# Misc.net
KiCad netlist of a schematic drawn in Altium Designer
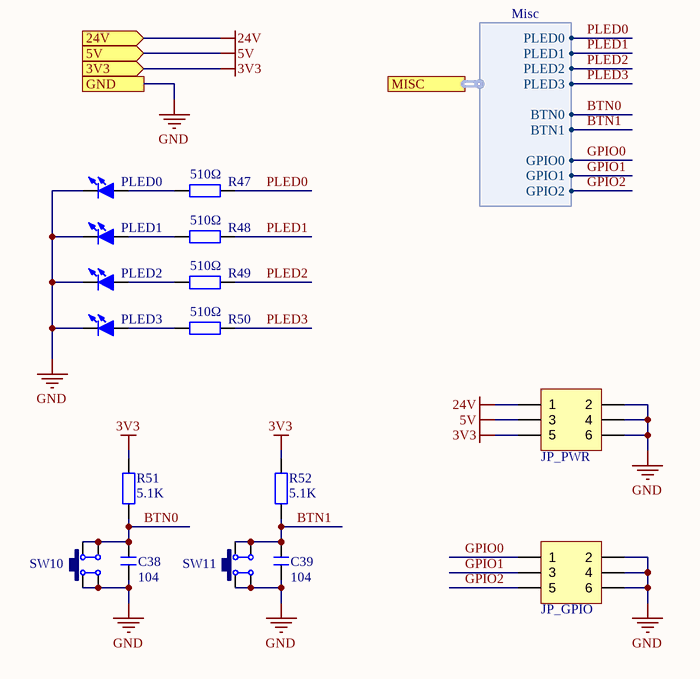
[diagram p0: Misc.SchDoc]

(export (version "E")
  (design (tool "Eeschema 10.0.6"))
  (components
    (comp (ref "C38")
      (value "104")
      (footprint "C 0603_L")
      (description "贴片电容")
      (libsource (lib "0.1 - 电阻-电容-电感") (part "C"))
    )
    (comp (ref "C39")
      (value "104")
      (footprint "C 0603_L")
      (description "贴片电容")
      (libsource (lib "0.1 - 电阻-电容-电感") (part "C"))
    )
    (comp (ref "JP_GPIO")
      (value "Header3X2")
      (footprint "HDR2.54-LI-2x3P")
      (description "3*2P接插件")
      (fields (field (name "版权归属") "封装库来自淘宝 ID：黄晶宝石"))
      (libsource (lib "5.4 - 接插件-脚距2.54 (100mil) ") (part "Header 3X2"))
    )
    (comp (ref "JP_PWR")
      (value "Header3X2")
      (footprint "HDR2.54-LI-2x3P")
      (description "3*2P接插件")
      (fields (field (name "版权归属") "封装库来自淘宝 ID：黄晶宝石"))
      (libsource (lib "5.4 - 接插件-脚距2.54 (100mil) ") (part "Header 3X2"))
    )
    (comp (ref "PLED0")
      (value "Green")
      (footprint "LED 0603G")
      (description "贴片LED")
      (fields (field (name "版权归属") "封装库来自淘宝 ID：黄晶宝石"))
      (libsource (lib "0.3 - LED发光二极管") (part "LED-SMD"))
    )
    (comp (ref "PLED1")
      (value "Green")
      (footprint "LED 0603G")
      (description "贴片LED")
      (fields (field (name "版权归属") "封装库来自淘宝 ID：黄晶宝石"))
      (libsource (lib "0.3 - LED发光二极管") (part "LED-SMD"))
    )
    (comp (ref "PLED2")
      (value "Green")
      (footprint "LED 0603G")
      (description "贴片LED")
      (fields (field (name "版权归属") "封装库来自淘宝 ID：黄晶宝石"))
      (libsource (lib "0.3 - LED发光二极管") (part "LED-SMD"))
    )
    (comp (ref "PLED3")
      (value "Green")
      (footprint "LED 0603G")
      (description "贴片LED")
      (fields (field (name "版权归属") "封装库来自淘宝 ID：黄晶宝石"))
      (libsource (lib "0.3 - LED发光二极管") (part "LED-SMD"))
    )
    (comp (ref "R47")
      (value "510Ω")
      (footprint "R 0603_L")
      (description "贴片电阻")
      (fields (field (name "版权归属") "来自淘宝 ID：黄晶宝石"))
      (libsource (lib "0.1 - 电阻-电容-电感") (part "R"))
    )
    (comp (ref "R48")
      (value "510Ω")
      (footprint "R 0603_L")
      (description "贴片电阻")
      (fields (field (name "版权归属") "来自淘宝 ID：黄晶宝石"))
      (libsource (lib "0.1 - 电阻-电容-电感") (part "R"))
    )
    (comp (ref "R49")
      (value "510Ω")
      (footprint "R 0603_L")
      (description "贴片电阻")
      (fields (field (name "版权归属") "来自淘宝 ID：黄晶宝石"))
      (libsource (lib "0.1 - 电阻-电容-电感") (part "R"))
    )
    (comp (ref "R50")
      (value "510Ω")
      (footprint "R 0603_L")
      (description "贴片电阻")
      (fields (field (name "版权归属") "来自淘宝 ID：黄晶宝石"))
      (libsource (lib "0.1 - 电阻-电容-电感") (part "R"))
    )
    (comp (ref "R51")
      (value "5.1K")
      (footprint "R 0603_L")
      (description "贴片电阻")
      (fields (field (name "版权归属") "来自淘宝 ID：黄晶宝石"))
      (libsource (lib "0.1 - 电阻-电容-电感") (part "R"))
    )
    (comp (ref "R52")
      (value "5.1K")
      (footprint "R 0603_L")
      (description "贴片电阻")
      (fields (field (name "版权归属") "来自淘宝 ID：黄晶宝石"))
      (libsource (lib "0.1 - 电阻-电容-电感") (part "R"))
    )
    (comp (ref "SW10")
      (value "6x6x5")
      (footprint "TSW SMD-6*6*4.3")
      (description "贴片6x6轻触开关 \r\nC3010208")
      (fields (field (name "版权归属") "封装库来自淘宝 ID：黄晶宝石"))
      (libsource (lib "0.7 - 常用按键-开关") (part "TSW SMD-6x6"))
    )
    (comp (ref "SW11")
      (value "6x6x5")
      (footprint "TSW SMD-6*6*4.3")
      (description "贴片6x6轻触开关 \r\nC3010208")
      (fields (field (name "版权归属") "封装库来自淘宝 ID：黄晶宝石"))
      (libsource (lib "0.7 - 常用按键-开关") (part "TSW SMD-6x6"))
    )
  )
  (nets
    (net (code "2") (name "/BTN0") (class "Default")
      (node (ref "C38") (pin "2") (pinfunction "2_2") (pintype "passive"))
      (node (ref "R51") (pin "1") (pinfunction "1_1") (pintype "passive"))
      (node (ref "SW10") (pin "2") (pinfunction "2_2") (pintype "passive"))
      (node (ref "SW10") (pin "3") (pinfunction "3_3") (pintype "passive"))
    )
    (net (code "3") (name "/BTN1") (class "Default")
      (node (ref "C39") (pin "2") (pinfunction "2_2") (pintype "passive"))
      (node (ref "R52") (pin "1") (pinfunction "1_1") (pintype "passive"))
      (node (ref "SW11") (pin "2") (pinfunction "2_2") (pintype "passive"))
      (node (ref "SW11") (pin "3") (pinfunction "3_3") (pintype "passive"))
    )
    (net (code "4") (name "/GPIO0") (class "Default")
      (node (ref "JP_GPIO") (pin "1") (pinfunction "1_1") (pintype "passive"))
    )
    (net (code "5") (name "/GPIO1") (class "Default")
      (node (ref "JP_GPIO") (pin "3") (pinfunction "3_3") (pintype "passive"))
    )
    (net (code "6") (name "/GPIO2") (class "Default")
      (node (ref "JP_GPIO") (pin "5") (pinfunction "5_5") (pintype "passive"))
    )
    (net (code "7") (name "/PLED0") (class "Default")
      (node (ref "R47") (pin "2") (pinfunction "2_2") (pintype "passive"))
    )
    (net (code "8") (name "/PLED1") (class "Default")
      (node (ref "R48") (pin "2") (pinfunction "2_2") (pintype "passive"))
    )
    (net (code "9") (name "/PLED2") (class "Default")
      (node (ref "R49") (pin "2") (pinfunction "2_2") (pintype "passive"))
    )
    (net (code "10") (name "/PLED3") (class "Default")
      (node (ref "R50") (pin "2") (pinfunction "2_2") (pintype "passive"))
    )
    (net (code "12") (name "3V3") (class "Default")
      (node (ref "JP_PWR") (pin "5") (pinfunction "5_5") (pintype "passive"))
      (node (ref "R51") (pin "2") (pinfunction "2_2") (pintype "passive"))
      (node (ref "R52") (pin "2") (pinfunction "2_2") (pintype "passive"))
    )
    (net (code "13") (name "5V") (class "Default")
      (node (ref "JP_PWR") (pin "3") (pinfunction "3_3") (pintype "passive"))
    )
    (net (code "14") (name "24V") (class "Default")
      (node (ref "JP_PWR") (pin "1") (pinfunction "1_1") (pintype "passive"))
    )
    (net (code "15") (name "GND") (class "Default")
      (node (ref "C38") (pin "1") (pinfunction "1_1") (pintype "passive"))
      (node (ref "C39") (pin "1") (pinfunction "1_1") (pintype "passive"))
      (node (ref "JP_GPIO") (pin "2") (pinfunction "2_2") (pintype "passive"))
      (node (ref "JP_GPIO") (pin "4") (pinfunction "4_4") (pintype "passive"))
      (node (ref "JP_GPIO") (pin "6") (pinfunction "6_6") (pintype "passive"))
      (node (ref "JP_PWR") (pin "2") (pinfunction "2_2") (pintype "passive"))
      (node (ref "JP_PWR") (pin "4") (pinfunction "4_4") (pintype "passive"))
      (node (ref "JP_PWR") (pin "6") (pinfunction "6_6") (pintype "passive"))
      (node (ref "PLED0") (pin "2") (pinfunction "K_2") (pintype "passive"))
      (node (ref "PLED1") (pin "2") (pinfunction "K_2") (pintype "passive"))
      (node (ref "PLED2") (pin "2") (pinfunction "K_2") (pintype "passive"))
      (node (ref "PLED3") (pin "2") (pinfunction "K_2") (pintype "passive"))
      (node (ref "SW10") (pin "1") (pinfunction "1_1") (pintype "passive"))
      (node (ref "SW10") (pin "4") (pinfunction "4_4") (pintype "passive"))
      (node (ref "SW11") (pin "1") (pinfunction "1_1") (pintype "passive"))
      (node (ref "SW11") (pin "4") (pinfunction "4_4") (pintype "passive"))
    )
    (net (code "16") (name "Net-(PLED0-A)") (class "Default")
      (node (ref "PLED0") (pin "1") (pinfunction "A_1") (pintype "passive"))
      (node (ref "R47") (pin "1") (pinfunction "1_1") (pintype "passive"))
    )
    (net (code "17") (name "Net-(PLED1-A)") (class "Default")
      (node (ref "PLED1") (pin "1") (pinfunction "A_1") (pintype "passive"))
      (node (ref "R48") (pin "1") (pinfunction "1_1") (pintype "passive"))
    )
    (net (code "18") (name "Net-(PLED2-A)") (class "Default")
      (node (ref "PLED2") (pin "1") (pinfunction "A_1") (pintype "passive"))
      (node (ref "R49") (pin "1") (pinfunction "1_1") (pintype "passive"))
    )
    (net (code "19") (name "Net-(PLED3-A)") (class "Default")
      (node (ref "PLED3") (pin "1") (pinfunction "A_1") (pintype "passive"))
      (node (ref "R50") (pin "1") (pinfunction "1_1") (pintype "passive"))
    )
  )
)
